# untitled.net
KiCad netlist of a schematic drawn in EAGLE
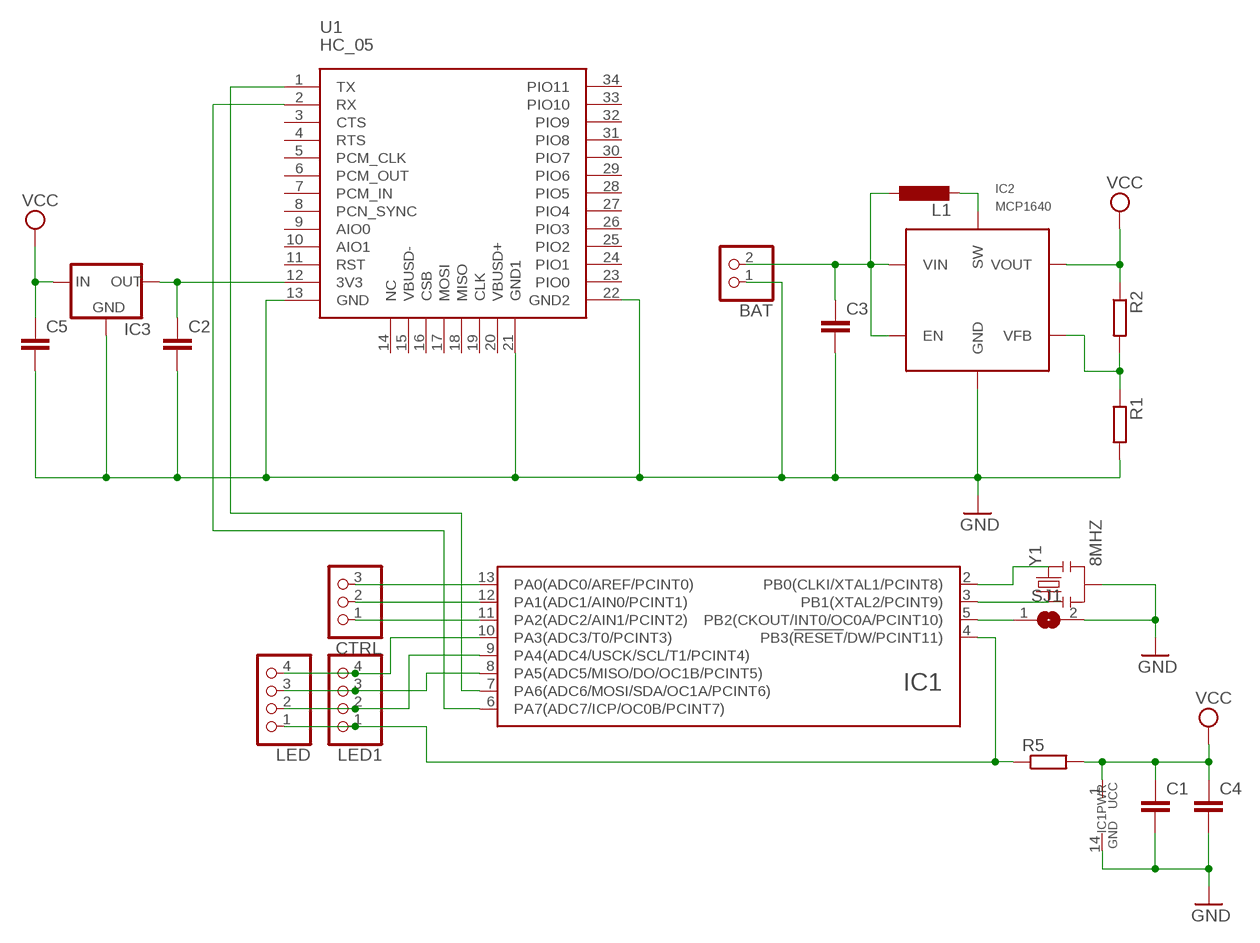
[diagram p0: schematic, sheet 1]

(export (version "E")
  (design (tool "Eeschema 10.0.6"))
  (components
    (comp (ref "BAT")
      (value "PINHD-1X2")
      (footprint "eagle-import:1X02")
      (libsource (lib "eagle-import") (part "PINHD-1X2"))
    )
    (comp (ref "C1")
      (value "C-EUC0805K")
      (footprint "eagle-import:C0805K")
      (libsource (lib "eagle-import") (part "C-EUC0805K"))
    )
    (comp (ref "C2")
      (value "C-EUC0805K")
      (footprint "eagle-import:C0805K")
      (libsource (lib "eagle-import") (part "C-EUC0805K"))
    )
    (comp (ref "C3")
      (value "C-EUC0805K")
      (footprint "eagle-import:C0805K")
      (libsource (lib "eagle-import") (part "C-EUC0805K"))
    )
    (comp (ref "C4")
      (value "C-EUC0805K")
      (footprint "eagle-import:C0805K")
      (libsource (lib "eagle-import") (part "C-EUC0805K"))
    )
    (comp (ref "C5")
      (value "C-EUC0805K")
      (footprint "eagle-import:C0805K")
      (libsource (lib "eagle-import") (part "C-EUC0805K"))
    )
    (comp (ref "CTRL")
      (value "PINHD-1X3")
      (footprint "eagle-import:1X03")
      (libsource (lib "eagle-import") (part "PINHD-1X3"))
    )
    (comp (ref "IC1")
      (value "ATTINY24/44/84-SSU")
      (footprint "eagle-import:SOIC14")
      (libsource (lib "eagle-import") (part "ATTINY24/44/84-SSU"))
    )
    (comp (ref "IC2")
      (value "MCP1640")
      (footprint "eagle-import:SOT23-6")
      (libsource (lib "eagle-import") (part "MCP1640"))
    )
    (comp (ref "IC3")
      (value "MCP1700_SOT-32")
      (footprint "eagle-import:SOT23")
      (libsource (lib "eagle-import") (part "MCP1700_SOT-32"))
    )
    (comp (ref "L1")
      (value "L-EU0204V")
      (footprint "eagle-import:0204V")
      (libsource (lib "eagle-import") (part "L-EU0204V"))
    )
    (comp (ref "LED")
      (value "PINHD-1X4")
      (footprint "eagle-import:1X04")
      (libsource (lib "eagle-import") (part "PINHD-1X4"))
    )
    (comp (ref "LED1")
      (value "PINHD-1X4")
      (footprint "eagle-import:1X04")
      (libsource (lib "eagle-import") (part "PINHD-1X4"))
    )
    (comp (ref "R1")
      (value "R-EU_M0805")
      (footprint "eagle-import:M0805")
      (libsource (lib "eagle-import") (part "R-EU_M0805"))
    )
    (comp (ref "R2")
      (value "R-EU_M0805")
      (footprint "eagle-import:M0805")
      (libsource (lib "eagle-import") (part "R-EU_M0805"))
    )
    (comp (ref "R5")
      (value "R-EU_M0805")
      (footprint "eagle-import:M0805")
      (libsource (lib "eagle-import") (part "R-EU_M0805"))
    )
    (comp (ref "SJ1") (value "SJ") (footprint "eagle-import:SJ") (libsource (lib "eagle-import") (part "SJ")))
    (comp (ref "U1")
      (value "HC_05")
      (footprint "eagle-import:BLUETOOTH_SMD")
      (libsource (lib "eagle-import") (part "HC_05"))
    )
    (comp (ref "Y1")
      (value "8MHZ")
      (footprint "eagle-import:RESONATOR-SMD")
      (libsource (lib "eagle-import") (part "RESONATOR8MHZ"))
    )
  )
  (nets
    (net (code "1") (name "GND") (class "Default")
      (node (ref "BAT") (pin "1") (pinfunction "1_1") (pintype "passive"))
      (node (ref "C1") (pin "2") (pinfunction "2_2") (pintype "passive"))
      (node (ref "C2") (pin "2") (pinfunction "2_2") (pintype "passive"))
      (node (ref "C3") (pin "2") (pinfunction "2_2") (pintype "passive"))
      (node (ref "C4") (pin "2") (pinfunction "2_2") (pintype "passive"))
      (node (ref "C5") (pin "2") (pinfunction "2_2") (pintype "passive"))
      (node (ref "IC1") (pin "14") (pinfunction "GND_14") (pintype "power_in"))
      (node (ref "IC2") (pin "2") (pinfunction "GND_2") (pintype "power_in"))
      (node (ref "IC3") (pin "1") (pinfunction "GND_1") (pintype "input"))
      (node (ref "R1") (pin "2") (pinfunction "2_2") (pintype "passive"))
      (node (ref "SJ1") (pin "2") (pinfunction "2_2") (pintype "passive"))
      (node (ref "U1") (pin "13") (pinfunction "GND_13") (pintype "bidirectional"))
      (node (ref "U1") (pin "21") (pinfunction "GND1_21") (pintype "bidirectional"))
      (node (ref "U1") (pin "22") (pinfunction "GND2_22") (pintype "bidirectional"))
      (node (ref "Y1") (pin "2") (pinfunction "2_2") (pintype "passive"))
    )
    (net (code "2") (name "Net-(IC1A-PA0(ADC0{slash}AREF{slash}PCINT0))") (class "Default")
      (node (ref "CTRL") (pin "3") (pinfunction "3_3") (pintype "passive"))
      (node (ref "IC1") (pin "13") (pinfunction "PA0(ADC0/AREF/PCINT0)_13") (pintype "bidirectional"))
    )
    (net (code "3") (name "Net-(IC1A-PA1(ADC1{slash}AIN0{slash}PCINT1))") (class "Default")
      (node (ref "CTRL") (pin "2") (pinfunction "2_2") (pintype "passive"))
      (node (ref "IC1") (pin "12") (pinfunction "PA1(ADC1/AIN0/PCINT1)_12") (pintype "bidirectional"))
    )
    (net (code "4") (name "Net-(IC1A-PA2(ADC2{slash}AIN1{slash}PCINT2))") (class "Default")
      (node (ref "CTRL") (pin "1") (pinfunction "1_1") (pintype "passive"))
      (node (ref "IC1") (pin "11") (pinfunction "PA2(ADC2/AIN1/PCINT2)_11") (pintype "bidirectional"))
    )
    (net (code "5") (name "Net-(IC1A-PA3(ADC3{slash}T0{slash}PCINT3))") (class "Default")
      (node (ref "IC1") (pin "10") (pinfunction "PA3(ADC3/T0/PCINT3)_10") (pintype "bidirectional"))
      (node (ref "LED") (pin "4") (pinfunction "4_4") (pintype "passive"))
      (node (ref "LED1") (pin "4") (pinfunction "4_4") (pintype "passive"))
    )
    (net (code "6") (name "Net-(IC1A-PA4(ADC4{slash}USCK{slash}SCL{slash}T1{slash}PCINT4))") (class "Default")
      (node (ref "IC1") (pin "9") (pinfunction "PA4(ADC4/USCK/SCL/T1/PCINT4)_9") (pintype "bidirectional"))
      (node (ref "LED") (pin "2") (pinfunction "2_2") (pintype "passive"))
      (node (ref "LED1") (pin "2") (pinfunction "2_2") (pintype "passive"))
    )
    (net (code "7") (name "Net-(IC1A-PA5(ADC5{slash}MISO{slash}DO{slash}OC1B{slash}PCINT5))") (class "Default")
      (node (ref "IC1") (pin "8") (pinfunction "PA5(ADC5/MISO/DO/OC1B/PCINT5)_8") (pintype "bidirectional"))
      (node (ref "LED") (pin "3") (pinfunction "3_3") (pintype "passive"))
      (node (ref "LED1") (pin "3") (pinfunction "3_3") (pintype "passive"))
    )
    (net (code "8") (name "Net-(IC1A-PA6(ADC6{slash}MOSI{slash}SDA{slash}OC1A{slash}PCINT6))") (class "Default")
      (node (ref "IC1") (pin "7") (pinfunction "PA6(ADC6/MOSI/SDA/OC1A/PCINT6)_7") (pintype "bidirectional"))
      (node (ref "U1") (pin "1") (pinfunction "TX_1") (pintype "bidirectional"))
    )
    (net (code "9") (name "Net-(IC1A-PA7(ADC7{slash}ICP{slash}OC0B{slash}PCINT7))") (class "Default")
      (node (ref "IC1") (pin "6") (pinfunction "PA7(ADC7/ICP/OC0B/PCINT7)_6") (pintype "bidirectional"))
      (node (ref "U1") (pin "2") (pinfunction "RX_2") (pintype "bidirectional"))
    )
    (net (code "10") (name "Net-(IC1A-PB0(CLKI{slash}XTAL1{slash}PCINT8))") (class "Default")
      (node (ref "IC1") (pin "2") (pinfunction "PB0(CLKI/XTAL1/PCINT8)_2") (pintype "bidirectional"))
      (node (ref "Y1") (pin "3") (pinfunction "3_3") (pintype "passive"))
    )
    (net (code "11") (name "Net-(IC1A-PB1(XTAL2{slash}PCINT9))") (class "Default")
      (node (ref "IC1") (pin "3") (pinfunction "PB1(XTAL2/PCINT9)_3") (pintype "bidirectional"))
      (node (ref "Y1") (pin "1") (pinfunction "1_1") (pintype "passive"))
    )
    (net (code "12") (name "Net-(IC1A-PB2(CKOUT{slash}INT0{slash}OC0A{slash}PCINT10))") (class "Default")
      (node (ref "IC1") (pin "5") (pinfunction "PB2(CKOUT/INT0/OC0A/PCINT10)_5") (pintype "bidirectional"))
      (node (ref "SJ1") (pin "1") (pinfunction "1_1") (pintype "passive"))
    )
    (net (code "13") (name "Net-(IC1A-PB3(~{RESET}{slash}DW{slash}PCINT11))") (class "Default")
      (node (ref "IC1") (pin "4") (pinfunction "PB3(~{RESET}/DW/PCINT11)_4") (pintype "bidirectional"))
      (node (ref "LED") (pin "1") (pinfunction "1_1") (pintype "passive"))
      (node (ref "LED1") (pin "1") (pinfunction "1_1") (pintype "passive"))
      (node (ref "R5") (pin "1") (pinfunction "1_1") (pintype "passive"))
    )
    (net (code "14") (name "Net-(IC2-EN)") (class "Default")
      (node (ref "BAT") (pin "2") (pinfunction "2_2") (pintype "passive"))
      (node (ref "C3") (pin "1") (pinfunction "1_1") (pintype "passive"))
      (node (ref "IC2") (pin "3") (pinfunction "EN_3") (pintype "input"))
      (node (ref "IC2") (pin "6") (pinfunction "VIN_6") (pintype "input"))
      (node (ref "L1") (pin "1") (pinfunction "1_1") (pintype "passive"))
    )
    (net (code "15") (name "Net-(IC2-SW)") (class "Default")
      (node (ref "IC2") (pin "1") (pinfunction "SW_1") (pintype "passive"))
      (node (ref "L1") (pin "2") (pinfunction "2_2") (pintype "passive"))
    )
    (net (code "16") (name "Net-(IC2-VFB)") (class "Default")
      (node (ref "IC2") (pin "4") (pinfunction "VFB_4") (pintype "input"))
      (node (ref "R1") (pin "1") (pinfunction "1_1") (pintype "passive"))
      (node (ref "R2") (pin "2") (pinfunction "2_2") (pintype "passive"))
    )
    (net (code "17") (name "Net-(IC3-OUT)") (class "Default")
      (node (ref "C2") (pin "1") (pinfunction "1_1") (pintype "passive"))
      (node (ref "IC3") (pin "2") (pinfunction "OUT_2") (pintype "passive"))
      (node (ref "U1") (pin "12") (pinfunction "3V3_12") (pintype "bidirectional"))
    )
    (net (code "18") (name "VCC") (class "Default")
      (node (ref "C1") (pin "1") (pinfunction "1_1") (pintype "passive"))
      (node (ref "C4") (pin "1") (pinfunction "1_1") (pintype "passive"))
      (node (ref "C5") (pin "1") (pinfunction "1_1") (pintype "passive"))
      (node (ref "IC1") (pin "1") (pinfunction "UCC_1") (pintype "power_in"))
      (node (ref "IC2") (pin "5") (pinfunction "VOUT_5") (pintype "power_in"))
      (node (ref "IC3") (pin "3") (pinfunction "IN_3") (pintype "input"))
      (node (ref "R2") (pin "1") (pinfunction "1_1") (pintype "passive"))
      (node (ref "R5") (pin "2") (pinfunction "2_2") (pintype "passive"))
    )
    (net (code "19") (name "unconnected-(U1-AIO0-Pad9)") (class "Default")
      (node (ref "U1") (pin "9") (pinfunction "AIO0_9") (pintype "bidirectional"))
    )
    (net (code "20") (name "unconnected-(U1-AIO1-Pad10)") (class "Default")
      (node (ref "U1") (pin "10") (pinfunction "AIO1_10") (pintype "bidirectional"))
    )
    (net (code "21") (name "unconnected-(U1-CLK-Pad19)") (class "Default")
      (node (ref "U1") (pin "19") (pinfunction "CLK_19") (pintype "bidirectional"))
    )
    (net (code "22") (name "unconnected-(U1-CSB-Pad16)") (class "Default")
      (node (ref "U1") (pin "16") (pinfunction "CSB_16") (pintype "bidirectional"))
    )
    (net (code "23") (name "unconnected-(U1-CTS-Pad3)") (class "Default")
      (node (ref "U1") (pin "3") (pinfunction "CTS_3") (pintype "bidirectional"))
    )
    (net (code "24") (name "unconnected-(U1-MISO-Pad18)") (class "Default")
      (node (ref "U1") (pin "18") (pinfunction "MISO_18") (pintype "bidirectional"))
    )
    (net (code "25") (name "unconnected-(U1-MOSI-Pad17)") (class "Default")
      (node (ref "U1") (pin "17") (pinfunction "MOSI_17") (pintype "bidirectional"))
    )
    (net (code "26") (name "unconnected-(U1-NC-Pad14)") (class "Default")
      (node (ref "U1") (pin "14") (pinfunction "NC_14") (pintype "bidirectional"))
    )
    (net (code "27") (name "unconnected-(U1-PCM_CLK-Pad5)") (class "Default")
      (node (ref "U1") (pin "5") (pinfunction "PCM_CLK_5") (pintype "bidirectional"))
    )
    (net (code "28") (name "unconnected-(U1-PCM_IN-Pad7)") (class "Default")
      (node (ref "U1") (pin "7") (pinfunction "PCM_IN_7") (pintype "bidirectional"))
    )
    (net (code "29") (name "unconnected-(U1-PCM_OUT-Pad6)") (class "Default")
      (node (ref "U1") (pin "6") (pinfunction "PCM_OUT_6") (pintype "bidirectional"))
    )
    (net (code "30") (name "unconnected-(U1-PCN_SYNC-Pad8)") (class "Default")
      (node (ref "U1") (pin "8") (pinfunction "PCN_SYNC_8") (pintype "bidirectional"))
    )
    (net (code "31") (name "unconnected-(U1-PIO0-Pad23)") (class "Default")
      (node (ref "U1") (pin "23") (pinfunction "PIO0_23") (pintype "bidirectional"))
    )
    (net (code "32") (name "unconnected-(U1-PIO1-Pad24)") (class "Default")
      (node (ref "U1") (pin "24") (pinfunction "PIO1_24") (pintype "bidirectional"))
    )
    (net (code "33") (name "unconnected-(U1-PIO2-Pad25)") (class "Default")
      (node (ref "U1") (pin "25") (pinfunction "PIO2_25") (pintype "bidirectional"))
    )
    (net (code "34") (name "unconnected-(U1-PIO3-Pad26)") (class "Default")
      (node (ref "U1") (pin "26") (pinfunction "PIO3_26") (pintype "bidirectional"))
    )
    (net (code "35") (name "unconnected-(U1-PIO4-Pad27)") (class "Default")
      (node (ref "U1") (pin "27") (pinfunction "PIO4_27") (pintype "bidirectional"))
    )
    (net (code "36") (name "unconnected-(U1-PIO5-Pad28)") (class "Default")
      (node (ref "U1") (pin "28") (pinfunction "PIO5_28") (pintype "bidirectional"))
    )
    (net (code "37") (name "unconnected-(U1-PIO6-Pad29)") (class "Default")
      (node (ref "U1") (pin "29") (pinfunction "PIO6_29") (pintype "bidirectional"))
    )
    (net (code "38") (name "unconnected-(U1-PIO7-Pad30)") (class "Default")
      (node (ref "U1") (pin "30") (pinfunction "PIO7_30") (pintype "bidirectional"))
    )
    (net (code "39") (name "unconnected-(U1-PIO8-Pad31)") (class "Default")
      (node (ref "U1") (pin "31") (pinfunction "PIO8_31") (pintype "bidirectional"))
    )
    (net (code "40") (name "unconnected-(U1-PIO9-Pad32)") (class "Default")
      (node (ref "U1") (pin "32") (pinfunction "PIO9_32") (pintype "bidirectional"))
    )
    (net (code "41") (name "unconnected-(U1-PIO10-Pad33)") (class "Default")
      (node (ref "U1") (pin "33") (pinfunction "PIO10_33") (pintype "bidirectional"))
    )
    (net (code "42") (name "unconnected-(U1-PIO11-Pad34)") (class "Default")
      (node (ref "U1") (pin "34") (pinfunction "PIO11_34") (pintype "bidirectional"))
    )
    (net (code "43") (name "unconnected-(U1-RST-Pad11)") (class "Default")
      (node (ref "U1") (pin "11") (pinfunction "RST_11") (pintype "bidirectional"))
    )
    (net (code "44") (name "unconnected-(U1-RTS-Pad4)") (class "Default")
      (node (ref "U1") (pin "4") (pinfunction "RTS_4") (pintype "bidirectional"))
    )
    (net (code "45") (name "unconnected-(U1-VBUSD+-Pad20)") (class "Default")
      (node (ref "U1") (pin "20") (pinfunction "VBUSD+_20") (pintype "bidirectional"))
    )
    (net (code "46") (name "unconnected-(U1-VBUSD--Pad15)") (class "Default")
      (node (ref "U1") (pin "15") (pinfunction "VBUSD-_15") (pintype "bidirectional"))
    )
  )
)
